# SENSORS.net
KiCad netlist of a schematic drawn in Altium Designer
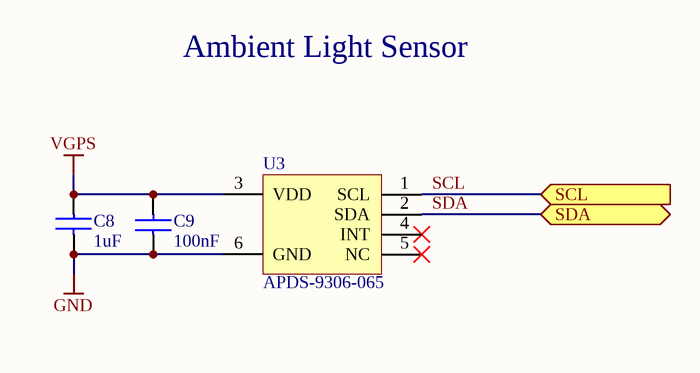
[diagram p0: SENSORS.SchDoc]

(export (version "E")
  (design (tool "Eeschema 10.0.6"))
  (components
    (comp (ref "C8")
      (value "1uF")
      (footprint "CAP0402")
      (description "CAP CER 1UF 10V 20% X5R 0402")
      (fields
        (field (name "MANUFACTURER") "Murata")
        (field (name "MANUFACTURER PART NUMBER") "GRM155R61A105ME15D")
      )
      (libsource (lib "Passive") (part "C - 1uF/0402"))
    )
    (comp (ref "C9")
      (value "100nF")
      (footprint "CAP0402")
      (fields
        (field (name "MANUFACTURER") "Multicomp")
        (field (name "MANUFACTURER PART NUMBER") "MC0402X104J160CT")
        (field (name "TOLERANCE") "5%")
      )
      (libsource (lib "Passive") (part "C - 100nF/0402"))
    )
    (comp (ref "U3")
      (value "APDS-9306-065")
      (footprint "APDS-9306")
      (description "Ambient Light Photo Sensor, Digital I2C Output, 560nm Peak Sensitivity, 1.7V to 3.6V Supply")
      (fields
        (field (name "MANUFACTURER") "TDK InvenSense")
        (field (name "MANUFACTURER PART NUMBER") "MPU-9250")
      )
      (libsource (lib "Active") (part "SEN - APDS-9306-065"))
    )
  )
  (nets
    (net (code "1") (name "/SCL") (class "Default")
      (node (ref "U3") (pin "1") (pinfunction "SCL_1") (pintype "passive"))
    )
    (net (code "2") (name "/SDA") (class "Default")
      (node (ref "U3") (pin "2") (pinfunction "SDA_2") (pintype "passive"))
    )
    (net (code "3") (name "GND") (class "Default")
      (node (ref "C8") (pin "2") (pinfunction "2_2") (pintype "passive"))
      (node (ref "C9") (pin "1") (pinfunction "1_1") (pintype "passive"))
      (node (ref "U3") (pin "6") (pinfunction "GND_6") (pintype "passive"))
    )
    (net (code "4") (name "VGPS") (class "Default")
      (node (ref "C8") (pin "1") (pinfunction "1_1") (pintype "passive"))
      (node (ref "C9") (pin "2") (pinfunction "2_2") (pintype "passive"))
      (node (ref "U3") (pin "3") (pinfunction "VDD_3") (pintype "passive"))
    )
    (net (code "5") (name "unconnected-(U3-INT-Pad4)") (class "Default")
      (node (ref "U3") (pin "4") (pinfunction "INT_4") (pintype "passive+no_connect"))
    )
    (net (code "6") (name "unconnected-(U3-NC-Pad5)") (class "Default")
      (node (ref "U3") (pin "5") (pinfunction "NC_5") (pintype "passive+no_connect"))
    )
  )
)
